# POWER.net
KiCad netlist of a schematic drawn in Altium Designer
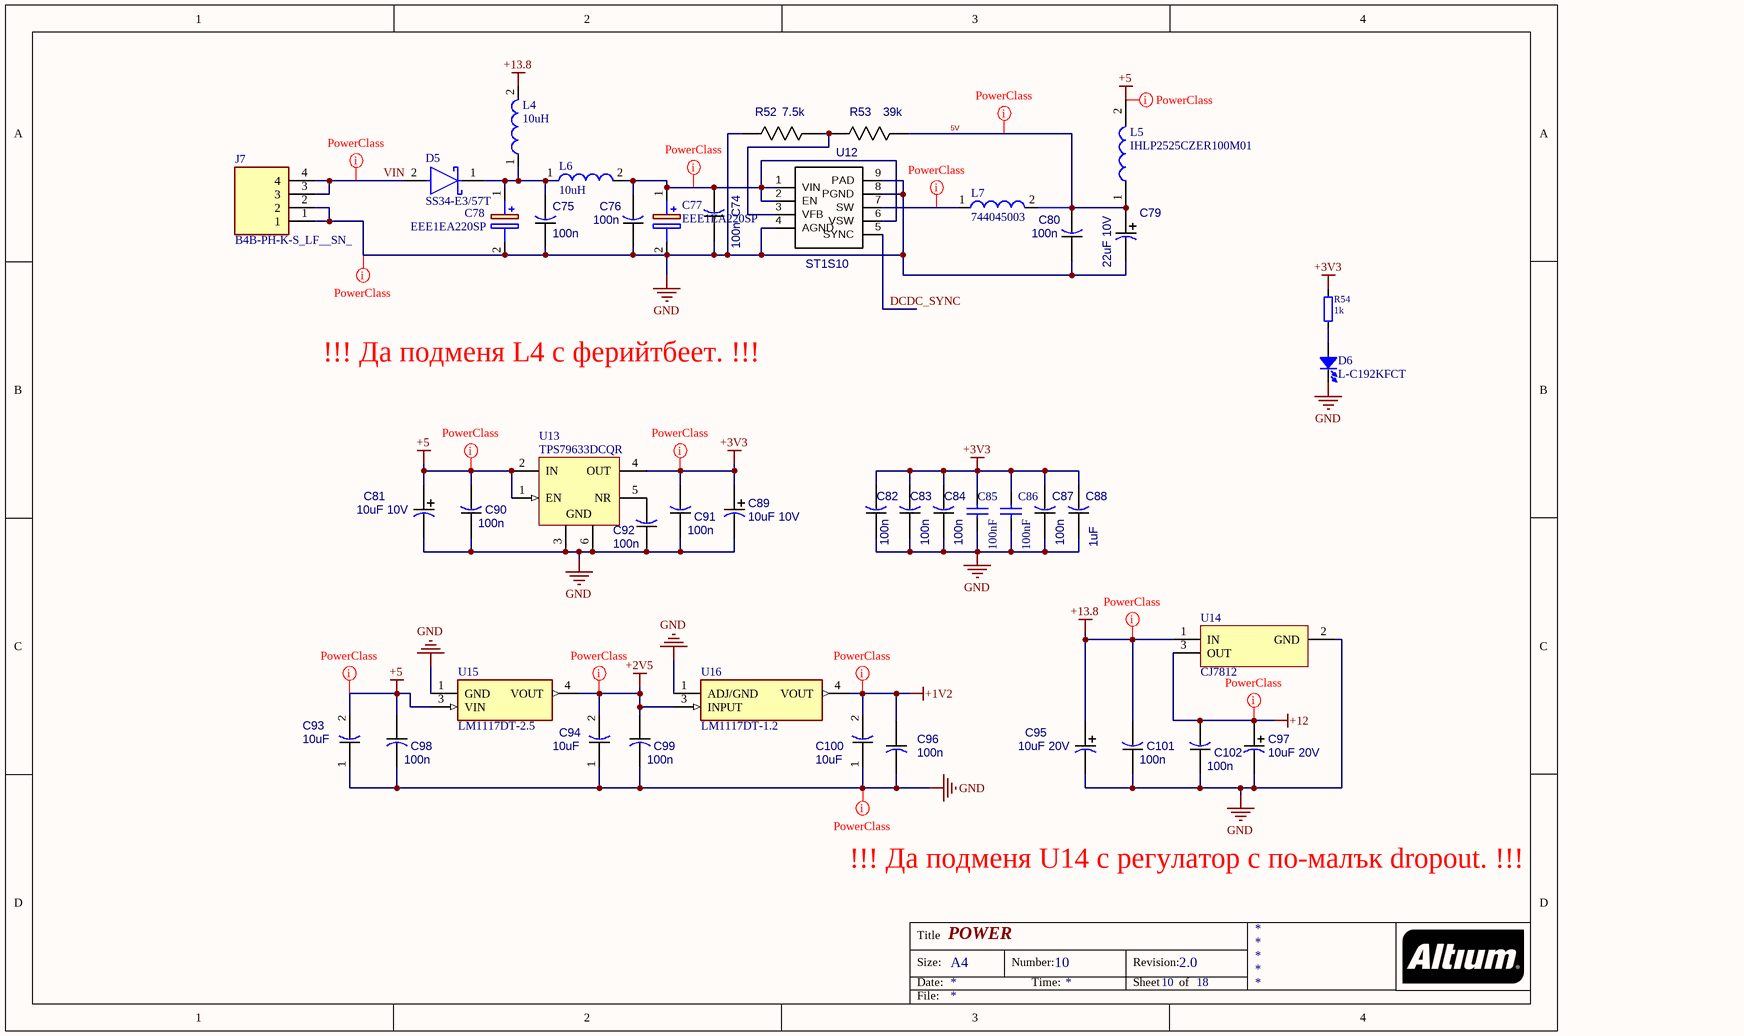
[diagram p0: POWER.SchDoc]

(export (version "E")
  (design (tool "Eeschema 10.0.6"))
  (components
    (comp (ref "C74")
      (value "100n")
      (footprint "CAP_0805")
      (description "CAP_0805")
      (libsource (lib "*") (part "CAP_0805"))
    )
    (comp (ref "C75")
      (value "100n")
      (footprint "CAP_0805")
      (description "CAP_0805")
      (libsource (lib "*") (part "CAP_0805"))
    )
    (comp (ref "C76")
      (value "100n")
      (footprint "CAP_0805")
      (description "CAP_0805")
      (libsource (lib "*") (part "CAP_0805"))
    )
    (comp (ref "C77")
      (value "EEE1EA220SP")
      (footprint "SamacSys:EEE1AA101SP")
      (description "Capacitor Polarised")
      (libsource (lib "SamacSys") (part "EEE1EA220SP"))
    )
    (comp (ref "C78")
      (value "EEE1EA220SP")
      (footprint "SamacSys:EEE1AA101SP")
      (description "Capacitor Polarised")
      (libsource (lib "SamacSys") (part "EEE1EA220SP"))
    )
    (comp (ref "C79")
      (value "22uF 10V")
      (footprint "CAPAE_4.3x4.3h5.4")
      (description "CAPAE_4.3x4.3h5.4")
      (libsource (lib "*") (part "CAPAE_4.3x4.3h5.4"))
    )
    (comp (ref "C80")
      (value "100n")
      (footprint "CAP_0805")
      (description "CAP_0805")
      (libsource (lib "*") (part "CAP_0805"))
    )
    (comp (ref "C81")
      (value "10uF 10V")
      (footprint "CAPAE_4.3x4.3h5.4")
      (description "CAPAE_4.3x4.3h5.4")
      (libsource (lib "*") (part "CAPAE_4.3x4.3h5.4"))
    )
    (comp (ref "C82")
      (value "100n")
      (footprint "CAP_0805")
      (description "CAP_0805")
      (libsource (lib "*") (part "CAP_0805"))
    )
    (comp (ref "C83")
      (value "100n")
      (footprint "CAP_0805")
      (description "CAP_0805")
      (libsource (lib "*") (part "CAP_0805"))
    )
    (comp (ref "C84")
      (value "100n")
      (footprint "CAP_0805")
      (description "CAP_0805")
      (libsource (lib "*") (part "CAP_0805"))
    )
    (comp (ref "C85")
      (value "100nF")
      (footprint "C-0603")
      (description "Ceramic Multilayer Capacitor")
      (fields (field (name "MANUFACTURER") "Yageo/Phycomp") (field (name "TOLERANCE") "±10%"))
      (libsource (lib "EXP-SX Power R2.4") (part "C semi"))
    )
    (comp (ref "C86")
      (value "100nF")
      (footprint "C-0603")
      (description "Ceramic Multilayer Capacitor")
      (fields (field (name "MANUFACTURER") "Yageo/Phycomp") (field (name "TOLERANCE") "±10%"))
      (libsource (lib "EXP-SX Power R2.4") (part "C semi"))
    )
    (comp (ref "C87")
      (value "100n")
      (footprint "CAP_0805")
      (description "CAP_0805")
      (libsource (lib "*") (part "CAP_0805"))
    )
    (comp (ref "C88")
      (value "1uF")
      (footprint "CAP_0805")
      (description "CAP_0805")
      (fields (field (name "Comment") "10uF"))
      (libsource (lib "*") (part "CAP_0805"))
    )
    (comp (ref "C89")
      (value "10uF 10V")
      (footprint "CAPAE_4.3x4.3h5.4")
      (description "CAPAE_4.3x4.3h5.4")
      (libsource (lib "*") (part "CAPAE_4.3x4.3h5.4"))
    )
    (comp (ref "C90")
      (value "100n")
      (footprint "CAP_0805")
      (description "CAP_0805")
      (libsource (lib "*") (part "CAP_0805"))
    )
    (comp (ref "C91")
      (value "100n")
      (footprint "CAP_0805")
      (description "CAP_0805")
      (libsource (lib "*") (part "CAP_0805"))
    )
    (comp (ref "C92")
      (value "100n")
      (footprint "CAP_0805")
      (description "CAP_0805")
      (libsource (lib "*") (part "CAP_0805"))
    )
    (comp (ref "C93")
      (value "10uF")
      (footprint "CAP_0805")
      (description "CAP_0805")
      (libsource (lib "MOTHERBOARD") (part "CAP_0805"))
    )
    (comp (ref "C94")
      (value "10uF")
      (footprint "CAP_0805")
      (description "CAP_0805")
      (libsource (lib "MOTHERBOARD") (part "CAP_0805"))
    )
    (comp (ref "C95")
      (value "10uF 20V")
      (footprint "CAPAE_4.3x4.3h5.4")
      (description "CAPAE_4.3x4.3h5.4")
      (libsource (lib "*") (part "CAPAE_4.3x4.3h5.4"))
    )
    (comp (ref "C96")
      (value "100n")
      (footprint "CAP_0805")
      (description "CAP_0805")
      (libsource (lib "*") (part "CAP_0805"))
    )
    (comp (ref "C97")
      (value "10uF 20V")
      (footprint "CAPAE_4.3x4.3h5.4")
      (description "CAPAE_4.3x4.3h5.4")
      (libsource (lib "*") (part "CAPAE_4.3x4.3h5.4"))
    )
    (comp (ref "C98")
      (value "100n")
      (footprint "CAP_0805")
      (description "CAP_0805")
      (libsource (lib "*") (part "CAP_0805"))
    )
    (comp (ref "C99")
      (value "100n")
      (footprint "CAP_0805")
      (description "CAP_0805")
      (libsource (lib "*") (part "CAP_0805"))
    )
    (comp (ref "C100")
      (value "10uF")
      (footprint "CAP_0805")
      (description "CAP_0805")
      (libsource (lib "MOTHERBOARD") (part "CAP_0805"))
    )
    (comp (ref "C101")
      (value "100n")
      (footprint "CAP_0805")
      (description "CAP_0805")
      (libsource (lib "*") (part "CAP_0805"))
    )
    (comp (ref "C102")
      (value "100n")
      (footprint "CAP_0805")
      (description "CAP_0805")
      (libsource (lib "*") (part "CAP_0805"))
    )
    (comp (ref "D5")
      (value "SS34-E3/57T")
      (footprint "FP-95402-MFG")
      (description "DIODE SCHOTTKY 40V 3A DO214AB")
      (fields
        (field (name "MANUFACTURER") "Vishay")
        (field (name "OCTOPART") "https://octopart.com/ss34-e3%2F57t-vishay-39552907")
      )
      (libsource (lib "Altium Content Vault") (part "1d6ec82d83fb6aee721767c19dac4b9"))
    )
    (comp (ref "D6")
      (value "L-C192KFCT")
      (footprint "LED 0603")
      (description "SMD LED Diode")
      (fields (field (name "MANUFACTURER") "Paralight"))
      (libsource (lib "Hristo") (part "D LED"))
    )
    (comp (ref "J7")
      (value "B4B-PH-K-S_LF__SN_")
      (footprint "SamacSys:SHDR4W50P0X200_1X4_990X450X600P")
      (description "Connector")
      (fields (field (name "MANUFACTURER_PART_NUMBER") "B4B-PH-K-S(LF)(SN)"))
      (libsource (lib "*") (part "B4B-PH-K-S_LF__SN_"))
    )
    (comp (ref "L4")
      (value "10uH")
      (footprint "WE-LQ-L")
      (description "SMD-RF-Inductor WE-LQ, L = 3.30 µH")
      (libsource (lib "Altium Content Vault") (part "PAS-IND-INDUCTOR-2"))
    )
    (comp (ref "L5")
      (value "IHLP2525CZER100M01")
      (footprint "SamacSys:INDPM6965X300N")
      (description "Inductor")
      (fields (field (name "MOUSER PART NUMBER") "70-IHLP2525CZER100M0"))
      (libsource (lib "SamacSys") (part "IHLP2525CZER100M01"))
    )
    (comp (ref "L6")
      (value "10uH")
      (footprint "WE-LQ-L")
      (description "SMD-RF-Inductor WE-LQ, L = 3.30 µH")
      (libsource (lib "Altium Content Vault") (part "PAS-IND-INDUCTOR-2"))
    )
    (comp (ref "L7")
      (value "744045003")
      (footprint "WE-LQ-L")
      (description "SMD-RF-Inductor WE-LQ, L = 3.30 µH")
      (libsource (lib "Altium Content Vault") (part "PAS-IND-INDUCTOR-2"))
    )
    (comp (ref "R52")
      (value "7.5k")
      (footprint "RES_0805")
      (description "RES_0805")
      (libsource (lib "*") (part "RES_0805"))
    )
    (comp (ref "R53")
      (value "39k")
      (footprint "RES_0805")
      (description "RES_0805")
      (libsource (lib "*") (part "RES_0805"))
    )
    (comp (ref "R54")
      (value "1k")
      (footprint "R-0805")
      (description "Chip Resistor")
      (fields (field (name "MANUFACTURER") "Yageo/Phycomp"))
      (libsource (lib "Hristo") (part "RES semi"))
    )
    (comp (ref "U12") (value "ST1S10") (footprint "ST1S10") (libsource (lib "*") (part "ST1S10")))
    (comp (ref "U13")
      (value "TPS79633DCQR")
      (footprint "DCQ0006A_L")
      (fields (field (name "MANUFACTURER") "Texas Instruments"))
      (libsource (lib "Altium Content Vault") (part "TI-TPS7XXXXXXXX"))
    )
    (comp (ref "U14")
      (value "CJ7812")
      (footprint "TO-252-2L")
      (libsource (lib "MOTHERBOARD") (part "CJ7812"))
    )
    (comp (ref "U15")
      (value "LM1117DT-2.5")
      (footprint "SamacSys:TO228P991X238-3N")
      (description "Integrated Circuit")
      (fields (field (name "MOUSER PART NUMBER") "926-LM1117DT-25"))
      (libsource (lib "*") (part "LM1117DT-2.5"))
    )
    (comp (ref "U16")
      (value "LM1117DT-1.2")
      (footprint "SamacSys:TO228P991X238-3N")
      (description "Integrated Circuit")
      (fields
        (field (name "MANUFACTURER_PART_NUMBER") "LM1117DT-1.8")
        (field (name "MOUSER PART NUMBER") "926-LM1117DT-18")
      )
      (libsource (lib "*") (part "LM1117DT-1.8"))
    )
  )
  (nets
    (net (code "1") (name "+1V2") (class "Default")
      (node (ref "C100") (pin "2") (pinfunction "2_2") (pintype "passive"))
      (node (ref "C96") (pin "1") (pinfunction "1_1") (pintype "passive"))
      (node (ref "U16") (pin "4") (pinfunction "VOUT_4") (pintype "output"))
    )
    (net (code "2") (name "+2V5") (class "Default")
      (node (ref "C94") (pin "2") (pinfunction "2_2") (pintype "passive"))
      (node (ref "C99") (pin "1") (pinfunction "1_1") (pintype "passive"))
      (node (ref "U15") (pin "4") (pinfunction "VOUT_4") (pintype "output"))
      (node (ref "U16") (pin "3") (pinfunction "INPUT_3") (pintype "input"))
    )
    (net (code "3") (name "+3V3") (class "Default")
      (node (ref "C82") (pin "2") (pinfunction "2_2") (pintype "passive"))
      (node (ref "C83") (pin "2") (pinfunction "2_2") (pintype "passive"))
      (node (ref "C84") (pin "2") (pinfunction "2_2") (pintype "passive"))
      (node (ref "C85") (pin "1") (pinfunction "1_1") (pintype "passive"))
      (node (ref "C86") (pin "1") (pinfunction "1_1") (pintype "passive"))
      (node (ref "C87") (pin "2") (pinfunction "2_2") (pintype "passive"))
      (node (ref "C88") (pin "2") (pinfunction "2_2") (pintype "passive"))
      (node (ref "C89") (pin "1") (pinfunction "PLUS_1") (pintype "passive"))
      (node (ref "C91") (pin "2") (pinfunction "2_2") (pintype "passive"))
      (node (ref "R54") (pin "2") (pinfunction "2_2") (pintype "passive"))
      (node (ref "U13") (pin "4") (pinfunction "OUT_4") (pintype "power_in"))
    )
    (net (code "4") (name "+5") (class "Default")
      (node (ref "C81") (pin "1") (pinfunction "PLUS_1") (pintype "passive"))
      (node (ref "C90") (pin "2") (pinfunction "2_2") (pintype "passive"))
      (node (ref "C93") (pin "2") (pinfunction "2_2") (pintype "passive"))
      (node (ref "C98") (pin "1") (pinfunction "1_1") (pintype "passive"))
      (node (ref "L5") (pin "2") (pinfunction "2_2") (pintype "passive"))
      (node (ref "U13") (pin "1") (pinfunction "EN_1") (pintype "input"))
      (node (ref "U13") (pin "2") (pinfunction "IN_2") (pintype "power_in"))
      (node (ref "U15") (pin "3") (pinfunction "VIN_3") (pintype "input"))
    )
    (net (code "5") (name "+12") (class "Default")
      (node (ref "C102") (pin "2") (pinfunction "2_2") (pintype "passive"))
      (node (ref "C97") (pin "1") (pinfunction "PLUS_1") (pintype "passive"))
      (node (ref "U14") (pin "3") (pinfunction "OUT_3") (pintype "passive"))
    )
    (net (code "6") (name "+13.8") (class "Default")
      (node (ref "C101") (pin "2") (pinfunction "2_2") (pintype "passive"))
      (node (ref "C95") (pin "1") (pinfunction "PLUS_1") (pintype "passive"))
      (node (ref "L4") (pin "2") (pinfunction "2_2") (pintype "passive"))
      (node (ref "U14") (pin "1") (pinfunction "IN_1") (pintype "passive"))
    )
    (net (code "7") (name "/5V") (class "Default")
      (node (ref "C79") (pin "1") (pinfunction "PLUS_1") (pintype "passive"))
      (node (ref "C80") (pin "2") (pinfunction "2_2") (pintype "passive"))
      (node (ref "L5") (pin "1") (pinfunction "1_1") (pintype "passive"))
      (node (ref "L7") (pin "2") (pinfunction "2_2") (pintype "passive"))
      (node (ref "R53") (pin "2") (pinfunction "2_2") (pintype "passive"))
    )
    (net (code "8") (name "/DCDC_SYNC") (class "Default")
      (node (ref "U12") (pin "5") (pinfunction "SYNC_5") (pintype "passive"))
    )
    (net (code "9") (name "/VIN") (class "Default")
      (node (ref "D5") (pin "2") (pinfunction "A_2") (pintype "passive"))
      (node (ref "J7") (pin "3") (pinfunction "3_3") (pintype "passive"))
      (node (ref "J7") (pin "4") (pinfunction "4_4") (pintype "passive"))
    )
    (net (code "10") (name "GND") (class "Default")
      (node (ref "C100") (pin "1") (pinfunction "1_1") (pintype "passive"))
      (node (ref "C101") (pin "1") (pinfunction "1_1") (pintype "passive"))
      (node (ref "C102") (pin "1") (pinfunction "1_1") (pintype "passive"))
      (node (ref "C74") (pin "1") (pinfunction "1_1") (pintype "passive"))
      (node (ref "C75") (pin "1") (pinfunction "1_1") (pintype "passive"))
      (node (ref "C76") (pin "1") (pinfunction "1_1") (pintype "passive"))
      (node (ref "C77") (pin "2") (pinfunction "-_2") (pintype "passive"))
      (node (ref "C78") (pin "2") (pinfunction "-_2") (pintype "passive"))
      (node (ref "C79") (pin "2") (pinfunction "MINUS_2") (pintype "passive"))
      (node (ref "C80") (pin "1") (pinfunction "1_1") (pintype "passive"))
      (node (ref "C81") (pin "2") (pinfunction "MINUS_2") (pintype "passive"))
      (node (ref "C82") (pin "1") (pinfunction "1_1") (pintype "passive"))
      (node (ref "C83") (pin "1") (pinfunction "1_1") (pintype "passive"))
      (node (ref "C84") (pin "1") (pinfunction "1_1") (pintype "passive"))
      (node (ref "C85") (pin "2") (pinfunction "2_2") (pintype "passive"))
      (node (ref "C86") (pin "2") (pinfunction "2_2") (pintype "passive"))
      (node (ref "C87") (pin "1") (pinfunction "1_1") (pintype "passive"))
      (node (ref "C88") (pin "1") (pinfunction "1_1") (pintype "passive"))
      (node (ref "C89") (pin "2") (pinfunction "MINUS_2") (pintype "passive"))
      (node (ref "C90") (pin "1") (pinfunction "1_1") (pintype "passive"))
      (node (ref "C91") (pin "1") (pinfunction "1_1") (pintype "passive"))
      (node (ref "C92") (pin "1") (pinfunction "1_1") (pintype "passive"))
      (node (ref "C93") (pin "1") (pinfunction "1_1") (pintype "passive"))
      (node (ref "C94") (pin "1") (pinfunction "1_1") (pintype "passive"))
      (node (ref "C95") (pin "2") (pinfunction "MINUS_2") (pintype "passive"))
      (node (ref "C96") (pin "2") (pinfunction "2_2") (pintype "passive"))
      (node (ref "C97") (pin "2") (pinfunction "MINUS_2") (pintype "passive"))
      (node (ref "C98") (pin "2") (pinfunction "2_2") (pintype "passive"))
      (node (ref "C99") (pin "2") (pinfunction "2_2") (pintype "passive"))
      (node (ref "D6") (pin "2") (pintype "passive"))
      (node (ref "J7") (pin "1") (pinfunction "1_1") (pintype "passive"))
      (node (ref "J7") (pin "2") (pinfunction "2_2") (pintype "passive"))
      (node (ref "R52") (pin "1") (pinfunction "1_1") (pintype "passive"))
      (node (ref "U12") (pin "4") (pinfunction "AGND_4") (pintype "passive"))
      (node (ref "U12") (pin "8") (pinfunction "PGND_8") (pintype "passive"))
      (node (ref "U12") (pin "9") (pinfunction "PAD_9") (pintype "passive"))
      (node (ref "U13") (pin "3") (pinfunction "GND_3") (pintype "power_in"))
      (node (ref "U13") (pin "6") (pinfunction "GND_6") (pintype "power_in"))
      (node (ref "U14") (pin "2") (pinfunction "GND_2") (pintype "passive"))
      (node (ref "U15") (pin "1") (pinfunction "GND_1") (pintype "power_in"))
      (node (ref "U16") (pin "1") (pinfunction "ADJ/GND_1") (pintype "power_in"))
    )
    (net (code "11") (name "Net-(C77-+)") (class "Default")
      (node (ref "C74") (pin "2") (pinfunction "2_2") (pintype "passive"))
      (node (ref "C76") (pin "2") (pinfunction "2_2") (pintype "passive"))
      (node (ref "C77") (pin "1") (pinfunction "+_1") (pintype "passive"))
      (node (ref "L6") (pin "2") (pinfunction "2_2") (pintype "passive"))
      (node (ref "U12") (pin "1") (pinfunction "VIN_1") (pintype "passive"))
      (node (ref "U12") (pin "2") (pinfunction "EN_2") (pintype "passive"))
      (node (ref "U12") (pin "6") (pinfunction "VSW_6") (pintype "passive"))
    )
    (net (code "12") (name "Net-(C78-+)") (class "Default")
      (node (ref "C75") (pin "2") (pinfunction "2_2") (pintype "passive"))
      (node (ref "C78") (pin "1") (pinfunction "+_1") (pintype "passive"))
      (node (ref "D5") (pin "1") (pinfunction "C_1") (pintype "passive"))
      (node (ref "L4") (pin "1") (pinfunction "1_1") (pintype "passive"))
      (node (ref "L6") (pin "1") (pinfunction "1_1") (pintype "passive"))
    )
    (net (code "13") (name "Net-(D6-Pad1)") (class "Default")
      (node (ref "D6") (pin "1") (pintype "passive"))
      (node (ref "R54") (pin "1") (pinfunction "1_1") (pintype "passive"))
    )
    (net (code "14") (name "Net-(U12-SW)") (class "Default")
      (node (ref "L7") (pin "1") (pinfunction "1_1") (pintype "passive"))
      (node (ref "U12") (pin "7") (pinfunction "SW_7") (pintype "passive"))
    )
    (net (code "15") (name "Net-(U12-VFB)") (class "Default")
      (node (ref "R52") (pin "2") (pinfunction "2_2") (pintype "passive"))
      (node (ref "R53") (pin "1") (pinfunction "1_1") (pintype "passive"))
      (node (ref "U12") (pin "3") (pinfunction "VFB_3") (pintype "passive"))
    )
    (net (code "16") (name "Net-(U13-NR)") (class "Default")
      (node (ref "C92") (pin "2") (pinfunction "2_2") (pintype "passive"))
      (node (ref "U13") (pin "5") (pinfunction "NR_5") (pintype "passive"))
    )
  )
)
